# schema.net
KiCad netlist of a schematic drawn in EAGLE
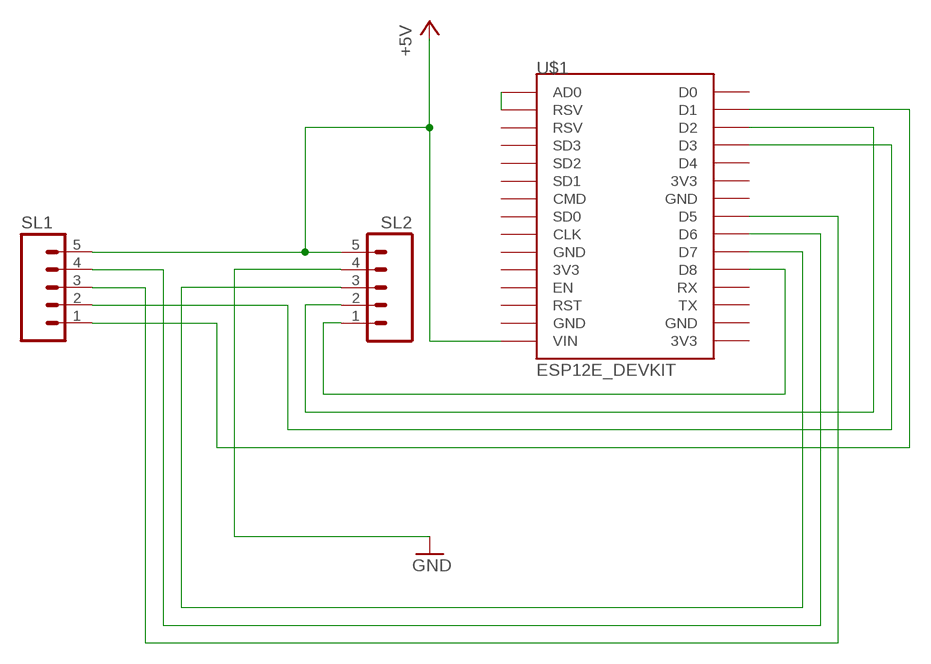
[diagram p0: schematic, sheet 1]

(export (version "E")
  (design (tool "Eeschema 10.0.6"))
  (components
    (comp (ref "SL1")
      (value "M05")
      (footprint "eagle-import:05P")
      (libsource (lib "eagle-import") (part "M05"))
    )
    (comp (ref "SL2")
      (value "M05")
      (footprint "eagle-import:05P")
      (libsource (lib "eagle-import") (part "M05"))
    )
    (comp (ref "U$1")
      (value "ESP12E_DEVKIT")
      (footprint "eagle-import:ESP12E_DEVKIT")
      (libsource (lib "eagle-import") (part "ESP12E_DEVKIT"))
    )
  )
  (nets
    (net (code "1") (name "+5V") (class "Default")
      (node (ref "SL1") (pin "5") (pinfunction "5_5") (pintype "passive"))
      (node (ref "SL2") (pin "5") (pinfunction "5_5") (pintype "passive"))
      (node (ref "U$1") (pin "VIN") (pinfunction "VIN_VIN") (pintype "bidirectional"))
    )
    (net (code "2") (name "GND") (class "Default")
      (node (ref "SL2") (pin "4") (pinfunction "4_4") (pintype "passive"))
    )
    (net (code "3") (name "Net-(SL1-Pad1)") (class "Default")
      (node (ref "SL1") (pin "1") (pinfunction "1_1") (pintype "passive"))
      (node (ref "U$1") (pin "D1") (pinfunction "D1_D1") (pintype "bidirectional"))
    )
    (net (code "4") (name "Net-(SL1-Pad2)") (class "Default")
      (node (ref "SL1") (pin "2") (pinfunction "2_2") (pintype "passive"))
      (node (ref "U$1") (pin "D3") (pinfunction "D3_D3") (pintype "bidirectional"))
    )
    (net (code "5") (name "Net-(SL1-Pad3)") (class "Default")
      (node (ref "SL1") (pin "3") (pinfunction "3_3") (pintype "passive"))
      (node (ref "U$1") (pin "D5") (pinfunction "D5_D5") (pintype "bidirectional"))
    )
    (net (code "6") (name "Net-(SL1-Pad4)") (class "Default")
      (node (ref "SL1") (pin "4") (pinfunction "4_4") (pintype "passive"))
      (node (ref "U$1") (pin "D6") (pinfunction "D6_D6") (pintype "bidirectional"))
    )
    (net (code "7") (name "Net-(SL2-Pad1)") (class "Default")
      (node (ref "SL2") (pin "1") (pinfunction "1_1") (pintype "passive"))
      (node (ref "U$1") (pin "D8") (pinfunction "D8_D8") (pintype "bidirectional"))
    )
    (net (code "8") (name "Net-(SL2-Pad2)") (class "Default")
      (node (ref "SL2") (pin "2") (pinfunction "2_2") (pintype "passive"))
      (node (ref "U$1") (pin "D2") (pinfunction "D2_D2") (pintype "bidirectional"))
    )
    (net (code "9") (name "Net-(SL2-Pad3)") (class "Default")
      (node (ref "SL2") (pin "3") (pinfunction "3_3") (pintype "passive"))
      (node (ref "U$1") (pin "D7") (pinfunction "D7_D7") (pintype "bidirectional"))
    )
    (net (code "10") (name "Net-(U$1-PadAD0)") (class "Default")
      (node (ref "U$1") (pin "AD0") (pinfunction "AD0_AD0") (pintype "bidirectional"))
      (node (ref "U$1") (pin "RSV@0") (pinfunction "RSV_RSV@0") (pintype "bidirectional"))
    )
    (net (code "11") (name "unconnected-(U$1-3V3-Pad3V3@0)") (class "Default")
      (node (ref "U$1") (pin "3V3@0") (pinfunction "3V3_3V3@0") (pintype "bidirectional"))
    )
    (net (code "12") (name "unconnected-(U$1-3V3-Pad3V3@1)") (class "Default")
      (node (ref "U$1") (pin "3V3@1") (pinfunction "3V3_3V3@1") (pintype "bidirectional"))
    )
    (net (code "13") (name "unconnected-(U$1-3V3-Pad3V3@2)") (class "Default")
      (node (ref "U$1") (pin "3V3@2") (pinfunction "3V3_3V3@2") (pintype "bidirectional"))
    )
    (net (code "14") (name "unconnected-(U$1-GND-PadGND@0)") (class "Default")
      (node (ref "U$1") (pin "GND@0") (pinfunction "GND_GND@0") (pintype "bidirectional"))
    )
    (net (code "15") (name "unconnected-(U$1-GND-PadGND@1)") (class "Default")
      (node (ref "U$1") (pin "GND@1") (pinfunction "GND_GND@1") (pintype "bidirectional"))
    )
    (net (code "16") (name "unconnected-(U$1-GND-PadGND@2)") (class "Default")
      (node (ref "U$1") (pin "GND@2") (pinfunction "GND_GND@2") (pintype "bidirectional"))
    )
    (net (code "17") (name "unconnected-(U$1-GND-PadGND@3)") (class "Default")
      (node (ref "U$1") (pin "GND@3") (pinfunction "GND_GND@3") (pintype "bidirectional"))
    )
    (net (code "18") (name "unconnected-(U$1-PadCLK)") (class "Default")
      (node (ref "U$1") (pin "CLK") (pinfunction "CLK_CLK") (pintype "bidirectional"))
    )
    (net (code "19") (name "unconnected-(U$1-PadCMD)") (class "Default")
      (node (ref "U$1") (pin "CMD") (pinfunction "CMD_CMD") (pintype "bidirectional"))
    )
    (net (code "20") (name "unconnected-(U$1-PadD0)") (class "Default")
      (node (ref "U$1") (pin "D0") (pinfunction "D0_D0") (pintype "bidirectional"))
    )
    (net (code "21") (name "unconnected-(U$1-PadD4)") (class "Default")
      (node (ref "U$1") (pin "D4") (pinfunction "D4_D4") (pintype "bidirectional"))
    )
    (net (code "22") (name "unconnected-(U$1-PadEN)") (class "Default")
      (node (ref "U$1") (pin "EN") (pinfunction "EN_EN") (pintype "bidirectional"))
    )
    (net (code "23") (name "unconnected-(U$1-PadRST)") (class "Default")
      (node (ref "U$1") (pin "RST") (pinfunction "RST_RST") (pintype "bidirectional"))
    )
    (net (code "24") (name "unconnected-(U$1-PadRX)") (class "Default")
      (node (ref "U$1") (pin "RX") (pinfunction "RX_RX") (pintype "bidirectional"))
    )
    (net (code "25") (name "unconnected-(U$1-PadSD0)") (class "Default")
      (node (ref "U$1") (pin "SD0") (pinfunction "SD0_SD0") (pintype "bidirectional"))
    )
    (net (code "26") (name "unconnected-(U$1-PadSD1)") (class "Default")
      (node (ref "U$1") (pin "SD1") (pinfunction "SD1_SD1") (pintype "bidirectional"))
    )
    (net (code "27") (name "unconnected-(U$1-PadSD2)") (class "Default")
      (node (ref "U$1") (pin "SD2") (pinfunction "SD2_SD2") (pintype "bidirectional"))
    )
    (net (code "28") (name "unconnected-(U$1-PadSD3)") (class "Default")
      (node (ref "U$1") (pin "SD3") (pinfunction "SD3_SD3") (pintype "bidirectional"))
    )
    (net (code "29") (name "unconnected-(U$1-PadTX)") (class "Default")
      (node (ref "U$1") (pin "TX") (pinfunction "TX_TX") (pintype "bidirectional"))
    )
    (net (code "30") (name "unconnected-(U$1-RSV-PadRSV@1)") (class "Default")
      (node (ref "U$1") (pin "RSV@1") (pinfunction "RSV_RSV@1") (pintype "bidirectional"))
    )
  )
)
